# LED_IO.net
KiCad netlist of a schematic drawn in Altium Designer
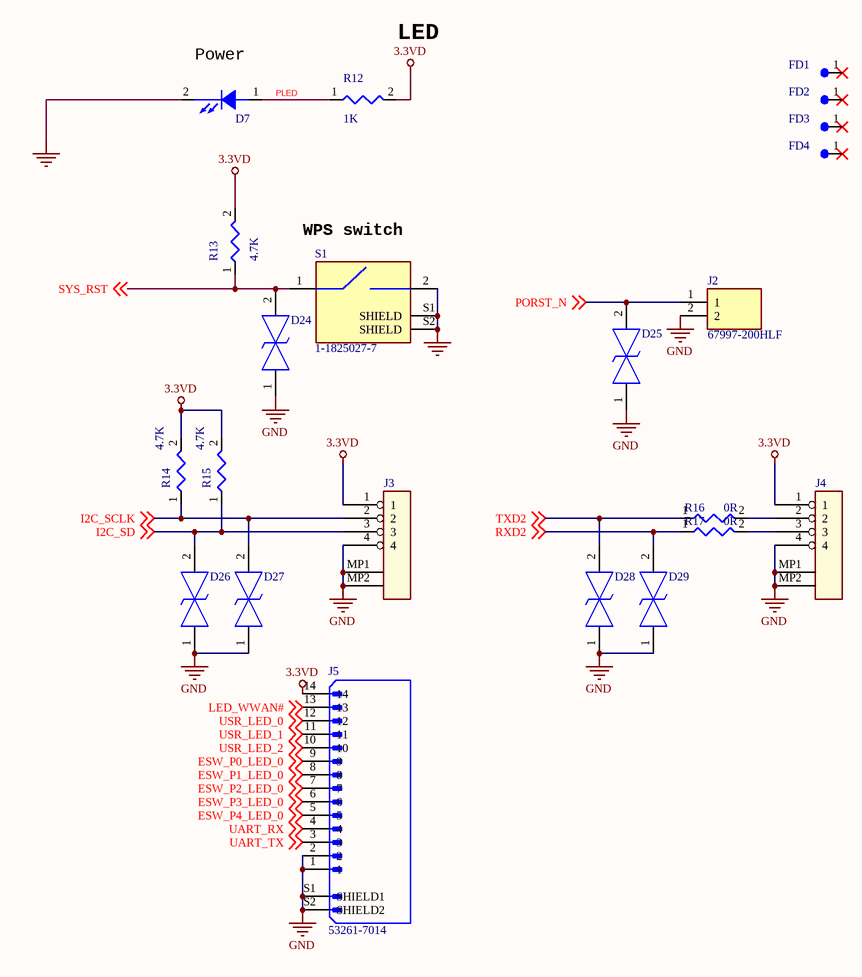
[diagram p0: LED_IO.SchDoc]

(export (version "E")
  (design (tool "Eeschema 10.0.6"))
  (components
    (comp (ref "D7") (value "LED/0603") (footprint "LED_0603") (libsource (lib "OOLITEV8") (part "LED/0603")))
    (comp (ref "D24")
      (value "ESD9B5VL-2_TR")
      (footprint "SamacSys:ESD9B5VL2TR")
      (description "TVS Diode (Bi-directional)")
      (fields (field (name "MANUFACTURER_PART_NUMBER") "ESD9B5VL-2/TR"))
      (libsource (lib "*") (part "ESD9B5VL-2_TR"))
    )
    (comp (ref "D25")
      (value "ESD9B5VL-2_TR")
      (footprint "SamacSys:ESD9B5VL2TR")
      (description "TVS Diode (Bi-directional)")
      (fields (field (name "MANUFACTURER_PART_NUMBER") "ESD9B5VL-2/TR"))
      (libsource (lib "*") (part "ESD9B5VL-2_TR"))
    )
    (comp (ref "D26")
      (value "ESD9B5VL-2_TR")
      (footprint "SamacSys:ESD9B5VL2TR")
      (description "TVS Diode (Bi-directional)")
      (fields (field (name "MANUFACTURER_PART_NUMBER") "ESD9B5VL-2/TR"))
      (libsource (lib "*") (part "ESD9B5VL-2_TR"))
    )
    (comp (ref "D27")
      (value "ESD9B5VL-2_TR")
      (footprint "SamacSys:ESD9B5VL2TR")
      (description "TVS Diode (Bi-directional)")
      (fields (field (name "MANUFACTURER_PART_NUMBER") "ESD9B5VL-2/TR"))
      (libsource (lib "*") (part "ESD9B5VL-2_TR"))
    )
    (comp (ref "D28")
      (value "ESD9B5VL-2_TR")
      (footprint "SamacSys:ESD9B5VL2TR")
      (description "TVS Diode (Bi-directional)")
      (fields (field (name "MANUFACTURER_PART_NUMBER") "ESD9B5VL-2/TR"))
      (libsource (lib "*") (part "ESD9B5VL-2_TR"))
    )
    (comp (ref "D29")
      (value "ESD9B5VL-2_TR")
      (footprint "SamacSys:ESD9B5VL2TR")
      (description "TVS Diode (Bi-directional)")
      (fields (field (name "MANUFACTURER_PART_NUMBER") "ESD9B5VL-2/TR"))
      (libsource (lib "*") (part "ESD9B5VL-2_TR"))
    )
    (comp (ref "FD1")
      (value "Fiducial")
      (footprint "FD")
      (libsource (lib "IIOT_GATEWAY_MT7621") (part "Fiducial"))
    )
    (comp (ref "FD2")
      (value "Fiducial")
      (footprint "FD")
      (libsource (lib "IIOT_GATEWAY_MT7621") (part "Fiducial"))
    )
    (comp (ref "FD3")
      (value "Fiducial")
      (footprint "FD")
      (libsource (lib "IIOT_GATEWAY_MT7621") (part "Fiducial"))
    )
    (comp (ref "FD4")
      (value "Fiducial")
      (footprint "FD")
      (libsource (lib "IIOT_GATEWAY_MT7621") (part "Fiducial"))
    )
    (comp (ref "J2")
      (value "67997-200HLF")
      (footprint "SamacSys:HDRV2W67P254_2X1_254X483X858P")
      (description "Connector")
      (fields (field (name "MOUSER PART NUMBER") "649-67997-200HLF"))
      (libsource (lib "*") (part "67997-200HLF"))
    )
    (comp (ref "J3")
      (value "0533980471")
      (footprint "0533980471")
      (description "Conn Shrouded Header (3 Sides) HDR 4 POS 1.25mm Solder ST Top Entry SMD PicoBlade™ T/R")
      (fields (field (name "MANUFACTURER") "Molex") (field (name "MANUFACTURER PART NUMBER") "53398-0471"))
      (libsource (lib "OOLITEV8") (part "0533980471"))
    )
    (comp (ref "J4")
      (value "0533980471")
      (footprint "0533980471")
      (description "Conn Shrouded Header (3 Sides) HDR 4 POS 1.25mm Solder ST Top Entry SMD PicoBlade™ T/R")
      (fields (field (name "MANUFACTURER") "Molex") (field (name "MANUFACTURER PART NUMBER") "53398-0471"))
      (libsource (lib "OOLITEV8_0_2-DEV-V1_1_17") (part "0533980471"))
    )
    (comp (ref "J5")
      (value "53261-7014")
      (footprint "MOLEX_532617014")
      (fields (field (name "MP") "532617014"))
      (libsource (lib "53261-7014") (part "53261-7014"))
    )
    (comp (ref "R12") (value "1K") (footprint "0402-R") (libsource (lib "OOLITEV8") (part "Res")))
    (comp (ref "R13") (value "4.7K") (footprint "0402-R") (libsource (lib "OOLITEV8") (part "Res")))
    (comp (ref "R14") (value "4.7K") (footprint "0603-R") (libsource (lib "OOLITEV8") (part "Res")))
    (comp (ref "R15") (value "4.7K") (footprint "0603-R") (libsource (lib "OOLITEV8") (part "Res")))
    (comp (ref "R16")
      (value "0R")
      (footprint "0402-R")
      (libsource (lib "OOLITEV8_0_2-DEV-V1_1_17") (part "Res"))
    )
    (comp (ref "R17")
      (value "0R")
      (footprint "0402-R")
      (libsource (lib "OOLITEV8_0_2-DEV-V1_1_17") (part "Res"))
    )
    (comp (ref "S1")
      (value "1-1825027-7")
      (footprint "118250277")
      (description "Switch")
      (fields (field (name "MOUSER PART NUMBER") "655-1-1825027-7"))
      (libsource (lib "OOLITEV8") (part "1-1825027-7"))
    )
  )
  (nets
    (net (code "1") (name "/PLED") (class "Default")
      (node (ref "D7") (pin "1") (pinfunction "ANODE_1") (pintype "passive"))
      (node (ref "R12") (pin "1") (pinfunction "1_1") (pintype "passive"))
    )
    (net (code "2") (name "3.3VD") (class "Default")
      (node (ref "J3") (pin "1") (pinfunction "1_1") (pintype "passive"))
      (node (ref "J4") (pin "1") (pinfunction "1_1") (pintype "passive"))
      (node (ref "J5") (pin "14") (pinfunction "14_14") (pintype "passive"))
      (node (ref "R12") (pin "2") (pinfunction "2_2") (pintype "passive"))
      (node (ref "R13") (pin "2") (pinfunction "2_2") (pintype "passive"))
      (node (ref "R14") (pin "2") (pinfunction "2_2") (pintype "passive"))
      (node (ref "R15") (pin "2") (pinfunction "2_2") (pintype "passive"))
    )
    (net (code "3") (name "ESW_P0_LED_0") (class "Default")
      (node (ref "J5") (pin "9") (pinfunction "9_9") (pintype "passive"))
    )
    (net (code "4") (name "ESW_P1_LED_0") (class "Default")
      (node (ref "J5") (pin "8") (pinfunction "8_8") (pintype "passive"))
    )
    (net (code "5") (name "ESW_P2_LED_0") (class "Default")
      (node (ref "J5") (pin "7") (pinfunction "7_7") (pintype "passive"))
    )
    (net (code "6") (name "ESW_P3_LED_0") (class "Default")
      (node (ref "J5") (pin "6") (pinfunction "6_6") (pintype "passive"))
    )
    (net (code "7") (name "ESW_P4_LED_0") (class "Default")
      (node (ref "J5") (pin "5") (pinfunction "5_5") (pintype "passive"))
    )
    (net (code "8") (name "GND") (class "Default")
      (node (ref "D24") (pin "1") (pinfunction "1_1") (pintype "passive"))
      (node (ref "D25") (pin "1") (pinfunction "1_1") (pintype "passive"))
      (node (ref "D26") (pin "1") (pinfunction "1_1") (pintype "passive"))
      (node (ref "D27") (pin "1") (pinfunction "1_1") (pintype "passive"))
      (node (ref "D28") (pin "1") (pinfunction "1_1") (pintype "passive"))
      (node (ref "D29") (pin "1") (pinfunction "1_1") (pintype "passive"))
      (node (ref "D7") (pin "2") (pinfunction "CATHODE_2") (pintype "passive"))
      (node (ref "J2") (pin "2") (pinfunction "2_2") (pintype "passive"))
      (node (ref "J3") (pin "4") (pinfunction "4_4") (pintype "passive"))
      (node (ref "J3") (pin "MP1") (pinfunction "MP1_MP1") (pintype "passive"))
      (node (ref "J3") (pin "MP2") (pinfunction "MP2_MP2") (pintype "passive"))
      (node (ref "J4") (pin "4") (pinfunction "4_4") (pintype "passive"))
      (node (ref "J4") (pin "MP1") (pinfunction "MP1_MP1") (pintype "passive"))
      (node (ref "J4") (pin "MP2") (pinfunction "MP2_MP2") (pintype "passive"))
      (node (ref "J5") (pin "1") (pinfunction "1_1") (pintype "passive"))
      (node (ref "J5") (pin "2") (pinfunction "2_2") (pintype "passive"))
      (node (ref "J5") (pin "S1") (pinfunction "SHIELD1_S1") (pintype "passive"))
      (node (ref "J5") (pin "S2") (pinfunction "SHIELD2_S2") (pintype "passive"))
      (node (ref "S1") (pin "2") (pinfunction "NO_2") (pintype "passive"))
      (node (ref "S1") (pin "S1") (pinfunction "SHIELD_S1") (pintype "passive"))
      (node (ref "S1") (pin "S2") (pinfunction "SHIELD_S2") (pintype "passive"))
    )
    (net (code "9") (name "I2C_SCLK") (class "Default")
      (node (ref "D27") (pin "2") (pinfunction "2_2") (pintype "passive"))
      (node (ref "J3") (pin "2") (pinfunction "2_2") (pintype "passive"))
      (node (ref "R14") (pin "1") (pinfunction "1_1") (pintype "passive"))
    )
    (net (code "10") (name "I2C_SD") (class "Default")
      (node (ref "D26") (pin "2") (pinfunction "2_2") (pintype "passive"))
      (node (ref "J3") (pin "3") (pinfunction "3_3") (pintype "passive"))
      (node (ref "R15") (pin "1") (pinfunction "1_1") (pintype "passive"))
    )
    (net (code "11") (name "LED_WWAN#") (class "Default")
      (node (ref "J5") (pin "13") (pinfunction "13_13") (pintype "passive"))
    )
    (net (code "12") (name "Net-(J4-Pad2)") (class "Default")
      (node (ref "J4") (pin "2") (pinfunction "2_2") (pintype "passive"))
      (node (ref "R16") (pin "2") (pinfunction "2_2") (pintype "passive"))
    )
    (net (code "13") (name "Net-(J4-Pad3)") (class "Default")
      (node (ref "J4") (pin "3") (pinfunction "3_3") (pintype "passive"))
      (node (ref "R17") (pin "2") (pinfunction "2_2") (pintype "passive"))
    )
    (net (code "14") (name "PORST_N") (class "Default")
      (node (ref "D25") (pin "2") (pinfunction "2_2") (pintype "passive"))
      (node (ref "J2") (pin "1") (pinfunction "1_1") (pintype "passive"))
    )
    (net (code "15") (name "RXD2") (class "Default")
      (node (ref "D29") (pin "2") (pinfunction "2_2") (pintype "passive"))
      (node (ref "R17") (pin "1") (pinfunction "1_1") (pintype "passive"))
    )
    (net (code "16") (name "SYS_RST") (class "Default")
      (node (ref "D24") (pin "2") (pinfunction "2_2") (pintype "passive"))
      (node (ref "R13") (pin "1") (pinfunction "1_1") (pintype "passive"))
      (node (ref "S1") (pin "1") (pinfunction "COM_1") (pintype "passive"))
    )
    (net (code "17") (name "TXD2") (class "Default")
      (node (ref "D28") (pin "2") (pinfunction "2_2") (pintype "passive"))
      (node (ref "R16") (pin "1") (pinfunction "1_1") (pintype "passive"))
    )
    (net (code "18") (name "UART_RX") (class "Default")
      (node (ref "J5") (pin "4") (pinfunction "4_4") (pintype "passive"))
    )
    (net (code "19") (name "UART_TX") (class "Default")
      (node (ref "J5") (pin "3") (pinfunction "3_3") (pintype "passive"))
    )
    (net (code "20") (name "USR_LED_0") (class "Default")
      (node (ref "J5") (pin "12") (pinfunction "12_12") (pintype "passive"))
    )
    (net (code "21") (name "USR_LED_1") (class "Default")
      (node (ref "J5") (pin "11") (pinfunction "11_11") (pintype "passive"))
    )
    (net (code "22") (name "USR_LED_2") (class "Default")
      (node (ref "J5") (pin "10") (pinfunction "10_10") (pintype "passive"))
    )
    (net (code "23") (name "unconnected-(FD1-Pad1)") (class "Default")
      (node (ref "FD1") (pin "1") (pinfunction "1_1") (pintype "passive+no_connect"))
    )
    (net (code "24") (name "unconnected-(FD2-Pad1)") (class "Default")
      (node (ref "FD2") (pin "1") (pinfunction "1_1") (pintype "passive+no_connect"))
    )
    (net (code "25") (name "unconnected-(FD3-Pad1)") (class "Default")
      (node (ref "FD3") (pin "1") (pinfunction "1_1") (pintype "passive+no_connect"))
    )
    (net (code "26") (name "unconnected-(FD4-Pad1)") (class "Default")
      (node (ref "FD4") (pin "1") (pinfunction "1_1") (pintype "passive+no_connect"))
    )
  )
)
